# final_v3.net
KiCad netlist of a schematic drawn in EAGLE
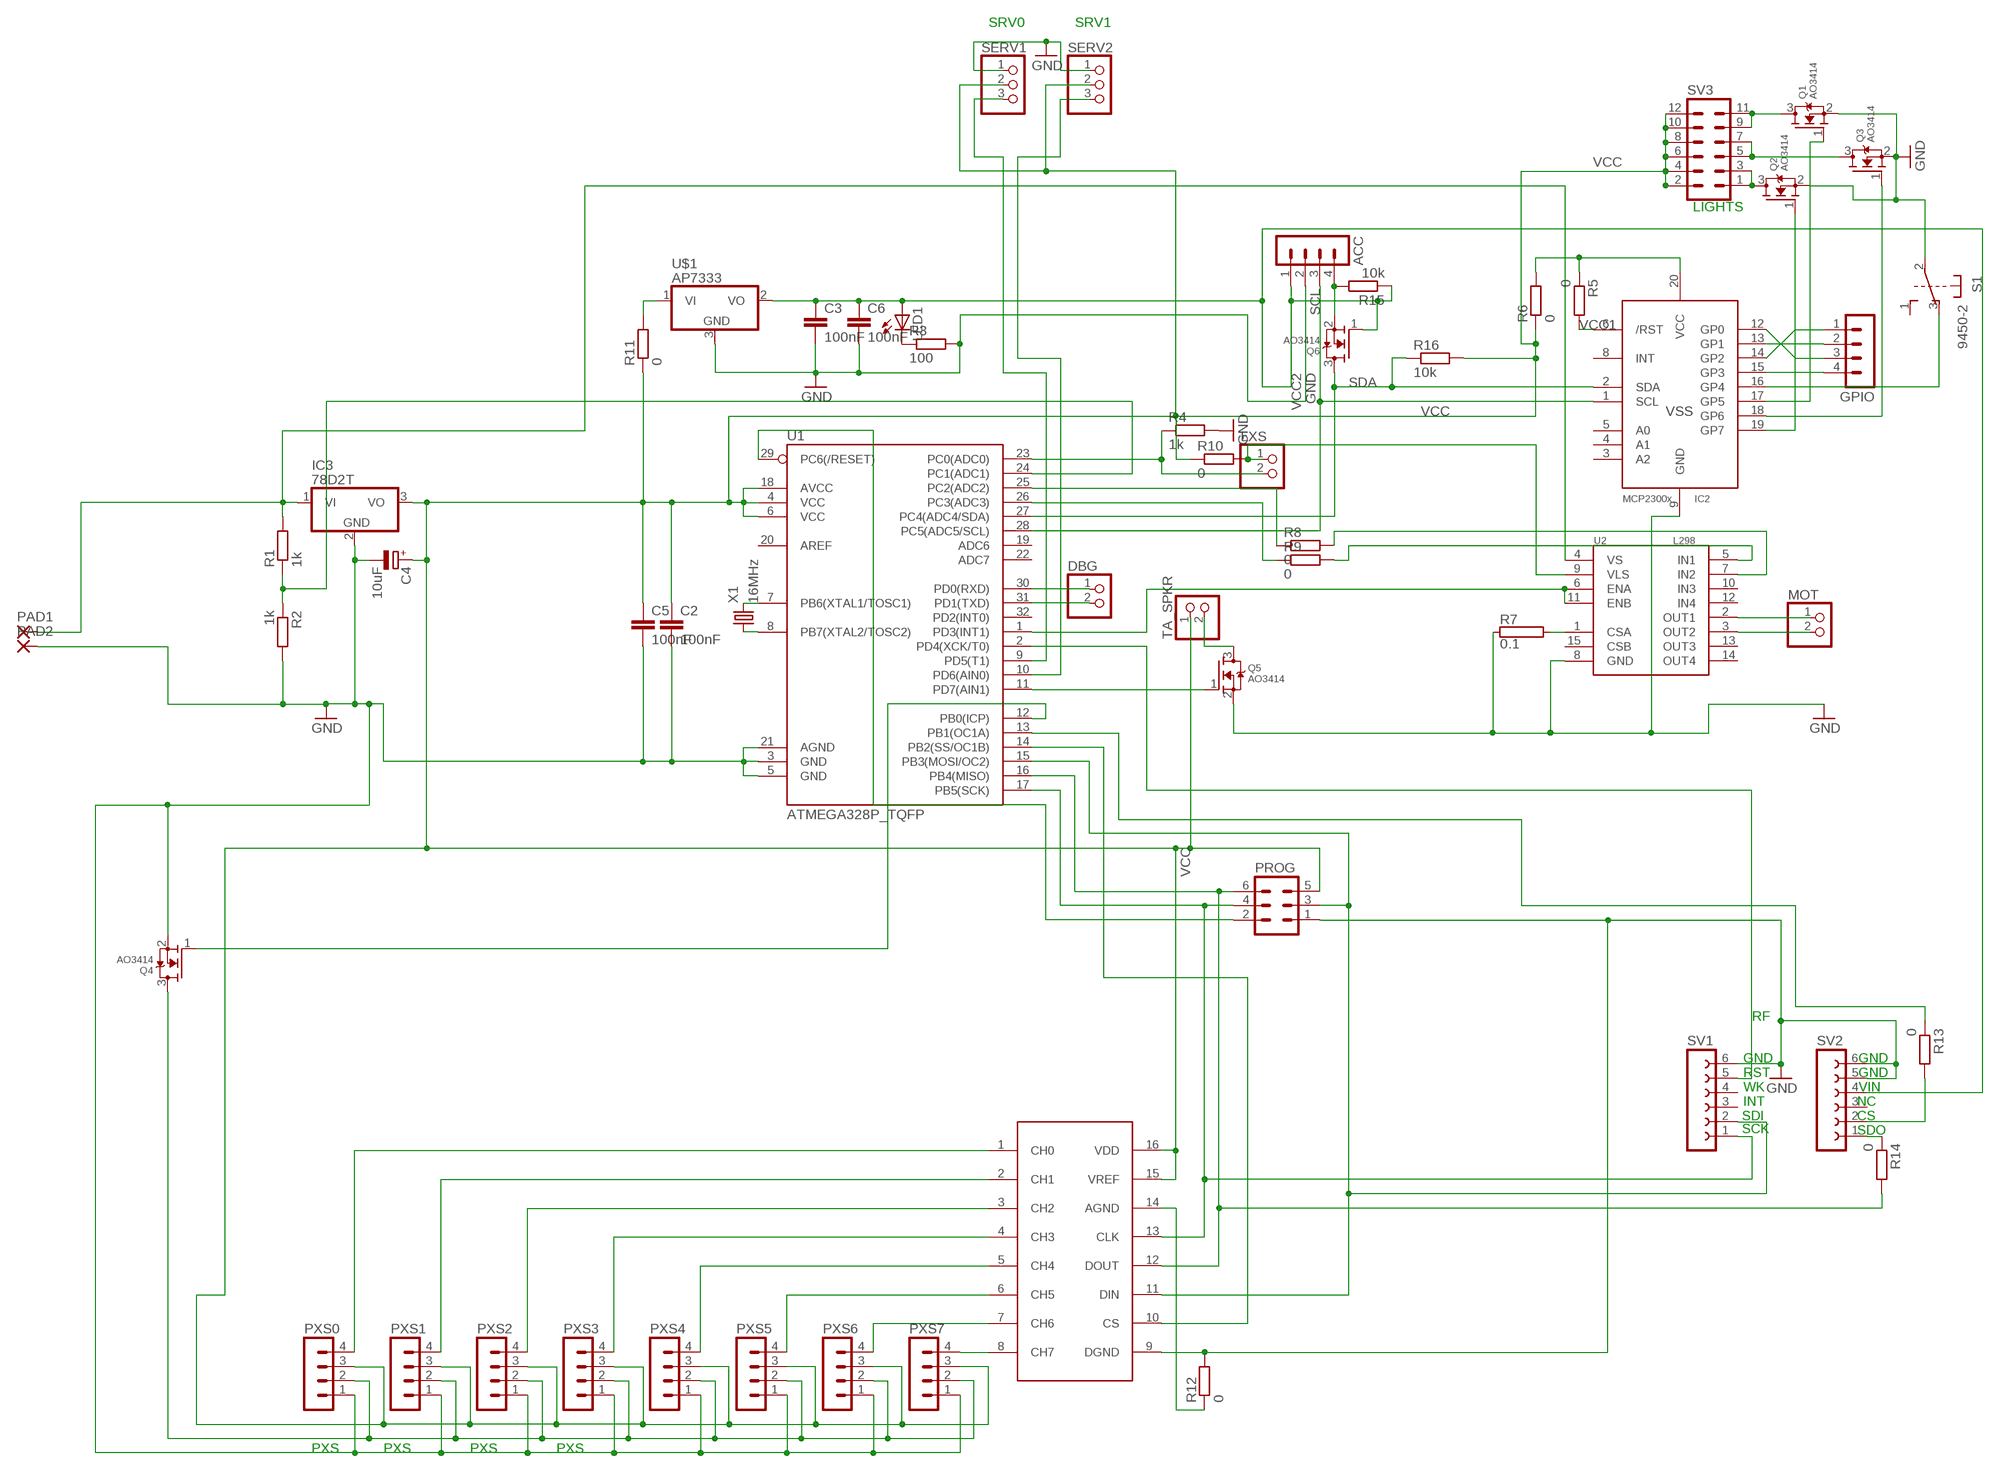
[diagram p0: schematic, sheet 1]

(export (version "E")
  (design (tool "Eeschema 10.0.6"))
  (components
    (comp (ref "ACC")
      (value "MA04-1")
      (footprint "eagle-import:MA04-1")
      (libsource (lib "eagle-import") (part "MA04-1"))
    )
    (comp (ref "C2")
      (value "100nF")
      (footprint "eagle-import:C1206")
      (libsource (lib "eagle-import") (part "C-EUC1206"))
    )
    (comp (ref "C3")
      (value "100nF")
      (footprint "eagle-import:C1206")
      (libsource (lib "eagle-import") (part "C-EUC1206"))
    )
    (comp (ref "C4")
      (value "10uF")
      (footprint "eagle-import:153CLV-0505")
      (libsource (lib "eagle-import") (part "CPOL-EU153CLV-0505"))
    )
    (comp (ref "C5")
      (value "100nF")
      (footprint "eagle-import:C1206")
      (libsource (lib "eagle-import") (part "C-EUC1206"))
    )
    (comp (ref "C6")
      (value "100nF")
      (footprint "eagle-import:C1206")
      (libsource (lib "eagle-import") (part "C-EUC1206"))
    )
    (comp (ref "DBG")
      (value "PINHD-1X2")
      (footprint "eagle-import:1X02")
      (libsource (lib "eagle-import") (part "PINHD-1X2"))
    )
    (comp (ref "GPIO")
      (value "MA04-1")
      (footprint "eagle-import:MA04-1")
      (libsource (lib "eagle-import") (part "MA04-1"))
    )
    (comp (ref "IC2")
      (value "MCP23008/SS")
      (footprint "eagle-import:SSOP20")
      (libsource (lib "eagle-import") (part "MCP23008/SS"))
    )
    (comp (ref "IC3")
      (value "78D2T")
      (footprint "eagle-import:D2PACK")
      (libsource (lib "eagle-import") (part "78D2T"))
    )
    (comp (ref "LED1")
      (value "LEDCHIPLED_0603")
      (footprint "eagle-import:CHIPLED_0603")
      (libsource (lib "eagle-import") (part "LEDCHIPLED_0603"))
    )
    (comp (ref "LXS")
      (value "PINHD-1X2")
      (footprint "eagle-import:1X02")
      (libsource (lib "eagle-import") (part "PINHD-1X2"))
    )
    (comp (ref "MOT")
      (value "PINHD-1X2")
      (footprint "eagle-import:1X02")
      (libsource (lib "eagle-import") (part "PINHD-1X2"))
    )
    (comp (ref "PAD1")
      (value "SMD5")
      (footprint "eagle-import:SMD2,54-5,08")
      (libsource (lib "eagle-import") (part "SMD5"))
    )
    (comp (ref "PAD2")
      (value "SMD5")
      (footprint "eagle-import:SMD2,54-5,08")
      (libsource (lib "eagle-import") (part "SMD5"))
    )
    (comp (ref "PROG")
      (value "MA03-2")
      (footprint "eagle-import:MA03-2")
      (libsource (lib "eagle-import") (part "MA03-2"))
    )
    (comp (ref "PXS0")
      (value "MA04-1")
      (footprint "eagle-import:MA04-1")
      (libsource (lib "eagle-import") (part "custom_MA04-1"))
    )
    (comp (ref "PXS1")
      (value "MA04-1")
      (footprint "eagle-import:MA04-1")
      (libsource (lib "eagle-import") (part "custom_MA04-1"))
    )
    (comp (ref "PXS2")
      (value "MA04-1")
      (footprint "eagle-import:MA04-1")
      (libsource (lib "eagle-import") (part "custom_MA04-1"))
    )
    (comp (ref "PXS3")
      (value "MA04-1")
      (footprint "eagle-import:MA04-1")
      (libsource (lib "eagle-import") (part "custom_MA04-1"))
    )
    (comp (ref "PXS4")
      (value "MA04-1")
      (footprint "eagle-import:MA04-1")
      (libsource (lib "eagle-import") (part "custom_MA04-1"))
    )
    (comp (ref "PXS5")
      (value "MA04-1")
      (footprint "eagle-import:MA04-1")
      (libsource (lib "eagle-import") (part "custom_MA04-1"))
    )
    (comp (ref "PXS6")
      (value "MA04-1")
      (footprint "eagle-import:MA04-1")
      (libsource (lib "eagle-import") (part "custom_MA04-1"))
    )
    (comp (ref "PXS7")
      (value "MA04-1")
      (footprint "eagle-import:MA04-1")
      (libsource (lib "eagle-import") (part "custom_MA04-1"))
    )
    (comp (ref "Q1")
      (value "AO3414")
      (footprint "eagle-import:SOT23")
      (libsource (lib "eagle-import") (part "MOSFET-NREFLOW"))
    )
    (comp (ref "Q2")
      (value "AO3414")
      (footprint "eagle-import:SOT23")
      (libsource (lib "eagle-import") (part "MOSFET-NREFLOW"))
    )
    (comp (ref "Q3")
      (value "AO3414")
      (footprint "eagle-import:SOT23")
      (libsource (lib "eagle-import") (part "MOSFET-NREFLOW"))
    )
    (comp (ref "Q4")
      (value "AO3414")
      (footprint "eagle-import:SOT23")
      (libsource (lib "eagle-import") (part "MOSFET-NREFLOW"))
    )
    (comp (ref "Q5")
      (value "AO3414")
      (footprint "eagle-import:SOT23")
      (libsource (lib "eagle-import") (part "MOSFET-NREFLOW"))
    )
    (comp (ref "Q6")
      (value "AO3414")
      (footprint "eagle-import:SOT23")
      (libsource (lib "eagle-import") (part "MOSFET-NREFLOW"))
    )
    (comp (ref "R1")
      (value "1k")
      (footprint "eagle-import:M1206")
      (libsource (lib "eagle-import") (part "resistor_R-EU_M1206"))
    )
    (comp (ref "R2")
      (value "1k")
      (footprint "eagle-import:R1206")
      (libsource (lib "eagle-import") (part "resistor_R-EU_R1206"))
    )
    (comp (ref "R3")
      (value "100")
      (footprint "eagle-import:R0603")
      (libsource (lib "eagle-import") (part "resistor_R-EU_R0603"))
    )
    (comp (ref "R4")
      (value "1k")
      (footprint "eagle-import:M1206")
      (libsource (lib "eagle-import") (part "resistor_R-EU_M1206"))
    )
    (comp (ref "R5")
      (value "0")
      (footprint "eagle-import:R0805BR")
      (libsource (lib "eagle-import") (part "R-EU_R0805BR"))
    )
    (comp (ref "R6")
      (value "0")
      (footprint "eagle-import:R0805BR")
      (libsource (lib "eagle-import") (part "R-EU_R0805BR"))
    )
    (comp (ref "R7")
      (value "0.1")
      (footprint "eagle-import:KH208R-8")
      (libsource (lib "eagle-import") (part "RKH208-8R"))
    )
    (comp (ref "R8")
      (value "0")
      (footprint "eagle-import:R0805BR")
      (libsource (lib "eagle-import") (part "R-EU_R0805BR"))
    )
    (comp (ref "R9")
      (value "0")
      (footprint "eagle-import:R0805BR")
      (libsource (lib "eagle-import") (part "R-EU_R0805BR"))
    )
    (comp (ref "R10")
      (value "0")
      (footprint "eagle-import:R0805BR")
      (libsource (lib "eagle-import") (part "R-EU_R0805BR"))
    )
    (comp (ref "R11")
      (value "0")
      (footprint "eagle-import:R0805BR")
      (libsource (lib "eagle-import") (part "R-EU_R0805BR"))
    )
    (comp (ref "R12")
      (value "0")
      (footprint "eagle-import:R0805BR")
      (libsource (lib "eagle-import") (part "R-EU_R0805BR"))
    )
    (comp (ref "R13")
      (value "0")
      (footprint "eagle-import:R0805BR")
      (libsource (lib "eagle-import") (part "R-EU_R0805BR"))
    )
    (comp (ref "R14")
      (value "0")
      (footprint "eagle-import:R0805BR")
      (libsource (lib "eagle-import") (part "R-EU_R0805BR"))
    )
    (comp (ref "R15")
      (value "10k")
      (footprint "eagle-import:R0805BR")
      (libsource (lib "eagle-import") (part "R-EU_R0805BR"))
    )
    (comp (ref "R16")
      (value "10k")
      (footprint "eagle-import:R0805BR")
      (libsource (lib "eagle-import") (part "R-EU_R0805BR"))
    )
    (comp (ref "S1")
      (value "9450-2")
      (footprint "eagle-import:9450-2")
      (libsource (lib "eagle-import") (part "9450-2"))
    )
    (comp (ref "SERV1")
      (value "PINHD-1X3")
      (footprint "eagle-import:1X03")
      (libsource (lib "eagle-import") (part "PINHD-1X3"))
    )
    (comp (ref "SERV2")
      (value "PINHD-1X3")
      (footprint "eagle-import:1X03")
      (libsource (lib "eagle-import") (part "PINHD-1X3"))
    )
    (comp (ref "SV1")
      (value "FE06-1")
      (footprint "eagle-import:FE06")
      (libsource (lib "eagle-import") (part "FE06-1"))
    )
    (comp (ref "SV2")
      (value "FE06-1")
      (footprint "eagle-import:FE06")
      (libsource (lib "eagle-import") (part "FE06-1"))
    )
    (comp (ref "SV3")
      (value "MA06-2")
      (footprint "eagle-import:MA06-2")
      (libsource (lib "eagle-import") (part "MA06-2"))
    )
    (comp (ref "TA_SPKR")
      (value "PINHD-1X2")
      (footprint "eagle-import:1X02")
      (libsource (lib "eagle-import") (part "PINHD-1X2"))
    )
    (comp (ref "U$1")
      (value "AP7333")
      (footprint "eagle-import:SOT23")
      (libsource (lib "eagle-import") (part "AP7333"))
    )
    (comp (ref "U$3")
      (value "MCP3208")
      (footprint "eagle-import:SO-16")
      (libsource (lib "eagle-import") (part "MCP3208"))
    )
    (comp (ref "U1")
      (value "ATMEGA328P_TQFP")
      (footprint "eagle-import:TQFP32-08")
      (libsource (lib "eagle-import") (part "ATMEGA328P_TQFP"))
    )
    (comp (ref "U2")
      (value "L298")
      (footprint "eagle-import:MULTIWATT15")
      (libsource (lib "eagle-import") (part "L298"))
    )
    (comp (ref "X1")
      (value "16MHz")
      (footprint "eagle-import:HC49_S")
      (libsource (lib "eagle-import") (part "CRYSTALHC49S"))
    )
  )
  (nets
    (net (code "1") (name "/SCL") (class "Default")
      (node (ref "ACC") (pin "3") (pinfunction "3_3") (pintype "passive"))
      (node (ref "IC2") (pin "1") (pinfunction "SCL_1") (pintype "bidirectional"))
      (node (ref "U1") (pin "28") (pinfunction "PC5(ADC5/SCL)_28") (pintype "bidirectional"))
    )
    (net (code "2") (name "/SDA") (class "Default")
      (node (ref "IC2") (pin "2") (pinfunction "SDA_2") (pintype "bidirectional"))
      (node (ref "Q6") (pin "3") (pinfunction "D_3") (pintype "bidirectional"))
      (node (ref "R16") (pin "1") (pinfunction "1_1") (pintype "passive"))
      (node (ref "U1") (pin "27") (pinfunction "PC4(ADC4/SDA)_27") (pintype "bidirectional"))
    )
    (net (code "3") (name "/VCC") (class "Default")
      (node (ref "C2") (pin "1") (pinfunction "1_1") (pintype "passive"))
      (node (ref "C4") (pin "+") (pinfunction "+_+") (pintype "passive"))
      (node (ref "C5") (pin "1") (pinfunction "1_1") (pintype "passive"))
      (node (ref "IC3") (pin "3") (pinfunction "VO_3") (pintype "passive"))
      (node (ref "PROG") (pin "5") (pinfunction "5_5") (pintype "passive"))
      (node (ref "PXS0") (pin "3") (pinfunction "3_3") (pintype "passive"))
      (node (ref "PXS1") (pin "3") (pinfunction "3_3") (pintype "passive"))
      (node (ref "PXS2") (pin "3") (pinfunction "3_3") (pintype "passive"))
      (node (ref "PXS3") (pin "3") (pinfunction "3_3") (pintype "passive"))
      (node (ref "PXS4") (pin "3") (pinfunction "3_3") (pintype "passive"))
      (node (ref "PXS5") (pin "3") (pinfunction "3_3") (pintype "passive"))
      (node (ref "PXS6") (pin "3") (pinfunction "3_3") (pintype "passive"))
      (node (ref "PXS7") (pin "3") (pinfunction "3_3") (pintype "passive"))
      (node (ref "R10") (pin "1") (pinfunction "1_1") (pintype "passive"))
      (node (ref "R11") (pin "1") (pinfunction "1_1") (pintype "passive"))
      (node (ref "R16") (pin "2") (pinfunction "2_2") (pintype "passive"))
      (node (ref "R6") (pin "1") (pinfunction "1_1") (pintype "passive"))
      (node (ref "SERV1") (pin "2") (pinfunction "2_2") (pintype "passive"))
      (node (ref "SERV2") (pin "2") (pinfunction "2_2") (pintype "passive"))
      (node (ref "SV3") (pin "10") (pinfunction "10_10") (pintype "passive"))
      (node (ref "SV3") (pin "12") (pinfunction "12_12") (pintype "passive"))
      (node (ref "SV3") (pin "2") (pinfunction "2_2") (pintype "passive"))
      (node (ref "SV3") (pin "4") (pinfunction "4_4") (pintype "passive"))
      (node (ref "SV3") (pin "6") (pinfunction "6_6") (pintype "passive"))
      (node (ref "SV3") (pin "8") (pinfunction "8_8") (pintype "passive"))
      (node (ref "TA_SPKR") (pin "1") (pinfunction "1_1") (pintype "passive"))
      (node (ref "U$3") (pin "15") (pinfunction "VREF_15") (pintype "bidirectional"))
      (node (ref "U$3") (pin "16") (pinfunction "VDD_16") (pintype "bidirectional"))
      (node (ref "U1") (pin "18") (pinfunction "AVCC_18") (pintype "bidirectional"))
      (node (ref "U1") (pin "4") (pinfunction "VCC_4") (pintype "bidirectional"))
      (node (ref "U1") (pin "6") (pinfunction "VCC_6") (pintype "bidirectional"))
    )
    (net (code "4") (name "/VCC1") (class "Default")
      (node (ref "IC2") (pin "6") (pinfunction "/RST_6") (pintype "input"))
      (node (ref "R5") (pin "2") (pinfunction "2_2") (pintype "passive"))
    )
    (net (code "5") (name "/VCC2") (class "Default")
      (node (ref "ACC") (pin "1") (pinfunction "1_1") (pintype "passive"))
      (node (ref "C3") (pin "1") (pinfunction "1_1") (pintype "passive"))
      (node (ref "C6") (pin "1") (pinfunction "1_1") (pintype "passive"))
      (node (ref "LED1") (pin "A") (pinfunction "A_A") (pintype "passive"))
      (node (ref "Q6") (pin "1") (pinfunction "G_1") (pintype "bidirectional"))
      (node (ref "R15") (pin "1") (pinfunction "1_1") (pintype "passive"))
      (node (ref "SV2") (pin "4") (pinfunction "4_4") (pintype "passive"))
      (node (ref "U$1") (pin "2") (pinfunction "VO_2") (pintype "passive"))
    )
    (net (code "6") (name "/VSS") (class "Default")
      (node (ref "IC3") (pin "1") (pinfunction "VI_1") (pintype "input"))
      (node (ref "PAD1") (pin "1") (pinfunction "P_1") (pintype "passive"))
      (node (ref "R1") (pin "2") (pinfunction "2_2") (pintype "passive"))
      (node (ref "U2") (pin "4") (pinfunction "VS_4") (pintype "bidirectional"))
    )
    (net (code "7") (name "GND") (class "Default")
      (node (ref "ACC") (pin "2") (pinfunction "2_2") (pintype "passive"))
      (node (ref "C2") (pin "2") (pinfunction "2_2") (pintype "passive"))
      (node (ref "C3") (pin "2") (pinfunction "2_2") (pintype "passive"))
      (node (ref "C4") (pin "-") (pinfunction "-_-") (pintype "passive"))
      (node (ref "C5") (pin "2") (pinfunction "2_2") (pintype "passive"))
      (node (ref "C6") (pin "2") (pinfunction "2_2") (pintype "passive"))
      (node (ref "IC2") (pin "9") (pinfunction "GND_9") (pintype "power_in"))
      (node (ref "IC3") (pin "2") (pinfunction "GND_2") (pintype "passive"))
      (node (ref "PAD2") (pin "1") (pinfunction "P_1") (pintype "passive"))
      (node (ref "PROG") (pin "1") (pinfunction "1_1") (pintype "passive"))
      (node (ref "PXS0") (pin "1") (pinfunction "1_1") (pintype "passive"))
      (node (ref "PXS1") (pin "1") (pinfunction "1_1") (pintype "passive"))
      (node (ref "PXS2") (pin "1") (pinfunction "1_1") (pintype "passive"))
      (node (ref "PXS3") (pin "1") (pinfunction "1_1") (pintype "passive"))
      (node (ref "PXS4") (pin "1") (pinfunction "1_1") (pintype "passive"))
      (node (ref "PXS5") (pin "1") (pinfunction "1_1") (pintype "passive"))
      (node (ref "PXS6") (pin "1") (pinfunction "1_1") (pintype "passive"))
      (node (ref "PXS7") (pin "1") (pinfunction "1_1") (pintype "passive"))
      (node (ref "Q1") (pin "2") (pinfunction "S_2") (pintype "bidirectional"))
      (node (ref "Q2") (pin "2") (pinfunction "S_2") (pintype "bidirectional"))
      (node (ref "Q3") (pin "2") (pinfunction "S_2") (pintype "bidirectional"))
      (node (ref "Q4") (pin "2") (pinfunction "S_2") (pintype "bidirectional"))
      (node (ref "Q5") (pin "2") (pinfunction "S_2") (pintype "bidirectional"))
      (node (ref "R12") (pin "2") (pinfunction "2_2") (pintype "passive"))
      (node (ref "R2") (pin "2") (pinfunction "2_2") (pintype "passive"))
      (node (ref "R3") (pin "2") (pinfunction "2_2") (pintype "passive"))
      (node (ref "R4") (pin "2") (pinfunction "2_2") (pintype "passive"))
      (node (ref "R7") (pin "1") (pinfunction "1_1") (pintype "passive"))
      (node (ref "S1") (pin "2") (pinfunction "P_2") (pintype "passive"))
      (node (ref "SERV1") (pin "1") (pinfunction "1_1") (pintype "passive"))
      (node (ref "SERV2") (pin "1") (pinfunction "1_1") (pintype "passive"))
      (node (ref "SV1") (pin "6") (pinfunction "6_6") (pintype "passive"))
      (node (ref "SV2") (pin "5") (pinfunction "5_5") (pintype "passive"))
      (node (ref "SV2") (pin "6") (pinfunction "6_6") (pintype "passive"))
      (node (ref "U$1") (pin "3") (pinfunction "GND_3") (pintype "passive"))
      (node (ref "U$3") (pin "9") (pinfunction "DGND_9") (pintype "bidirectional"))
      (node (ref "U1") (pin "21") (pinfunction "AGND_21") (pintype "bidirectional"))
      (node (ref "U1") (pin "3") (pinfunction "GND_3") (pintype "bidirectional"))
      (node (ref "U1") (pin "5") (pinfunction "GND_5") (pintype "bidirectional"))
      (node (ref "U2") (pin "8") (pinfunction "GND_8") (pintype "bidirectional"))
    )
    (net (code "8") (name "Net-(IC2-GP0)") (class "Default")
      (node (ref "GPIO") (pin "3") (pinfunction "3_3") (pintype "passive"))
      (node (ref "IC2") (pin "12") (pinfunction "GP0_12") (pintype "bidirectional"))
    )
    (net (code "9") (name "Net-(IC2-GP1)") (class "Default")
      (node (ref "GPIO") (pin "2") (pinfunction "2_2") (pintype "passive"))
      (node (ref "IC2") (pin "13") (pinfunction "GP1_13") (pintype "bidirectional"))
    )
    (net (code "10") (name "Net-(IC2-GP2)") (class "Default")
      (node (ref "GPIO") (pin "1") (pinfunction "1_1") (pintype "passive"))
      (node (ref "IC2") (pin "14") (pinfunction "GP2_14") (pintype "bidirectional"))
    )
    (net (code "11") (name "Net-(IC2-GP3)") (class "Default")
      (node (ref "GPIO") (pin "4") (pinfunction "4_4") (pintype "passive"))
      (node (ref "IC2") (pin "15") (pinfunction "GP3_15") (pintype "bidirectional"))
    )
    (net (code "12") (name "Net-(IC2-GP4)") (class "Default")
      (node (ref "IC2") (pin "16") (pinfunction "GP4_16") (pintype "bidirectional"))
      (node (ref "S1") (pin "3") (pinfunction "O_3") (pintype "passive"))
    )
    (net (code "13") (name "Net-(IC2-GP5)") (class "Default")
      (node (ref "IC2") (pin "17") (pinfunction "GP5_17") (pintype "bidirectional"))
      (node (ref "Q1") (pin "1") (pinfunction "G_1") (pintype "bidirectional"))
    )
    (net (code "14") (name "Net-(IC2-GP6)") (class "Default")
      (node (ref "IC2") (pin "18") (pinfunction "GP6_18") (pintype "bidirectional"))
      (node (ref "Q3") (pin "1") (pinfunction "G_1") (pintype "bidirectional"))
    )
    (net (code "15") (name "Net-(IC2-GP7)") (class "Default")
      (node (ref "IC2") (pin "19") (pinfunction "GP7_19") (pintype "bidirectional"))
      (node (ref "Q2") (pin "1") (pinfunction "G_1") (pintype "bidirectional"))
    )
    (net (code "16") (name "Net-(IC2-VCC)") (class "Default")
      (node (ref "IC2") (pin "20") (pinfunction "VCC_20") (pintype "power_in"))
      (node (ref "R5") (pin "1") (pinfunction "1_1") (pintype "passive"))
      (node (ref "R6") (pin "2") (pinfunction "2_2") (pintype "passive"))
    )
    (net (code "17") (name "Net-(LED1-PadC)") (class "Default")
      (node (ref "LED1") (pin "C") (pinfunction "C_C") (pintype "passive"))
      (node (ref "R3") (pin "1") (pinfunction "1_1") (pintype "passive"))
    )
    (net (code "18") (name "Net-(Q1-D)") (class "Default")
      (node (ref "Q1") (pin "3") (pinfunction "D_3") (pintype "bidirectional"))
      (node (ref "SV3") (pin "11") (pinfunction "11_11") (pintype "passive"))
      (node (ref "SV3") (pin "9") (pinfunction "9_9") (pintype "passive"))
    )
    (net (code "19") (name "Net-(Q2-D)") (class "Default")
      (node (ref "Q2") (pin "3") (pinfunction "D_3") (pintype "bidirectional"))
      (node (ref "SV3") (pin "1") (pinfunction "1_1") (pintype "passive"))
      (node (ref "SV3") (pin "3") (pinfunction "3_3") (pintype "passive"))
    )
    (net (code "20") (name "Net-(Q3-D)") (class "Default")
      (node (ref "Q3") (pin "3") (pinfunction "D_3") (pintype "bidirectional"))
      (node (ref "SV3") (pin "5") (pinfunction "5_5") (pintype "passive"))
      (node (ref "SV3") (pin "7") (pinfunction "7_7") (pintype "passive"))
    )
    (net (code "21") (name "Net-(Q4-D)") (class "Default")
      (node (ref "PXS0") (pin "2") (pinfunction "2_2") (pintype "passive"))
      (node (ref "PXS1") (pin "2") (pinfunction "2_2") (pintype "passive"))
      (node (ref "PXS2") (pin "2") (pinfunction "2_2") (pintype "passive"))
      (node (ref "PXS3") (pin "2") (pinfunction "2_2") (pintype "passive"))
      (node (ref "PXS4") (pin "2") (pinfunction "2_2") (pintype "passive"))
      (node (ref "PXS5") (pin "2") (pinfunction "2_2") (pintype "passive"))
      (node (ref "PXS6") (pin "2") (pinfunction "2_2") (pintype "passive"))
      (node (ref "PXS7") (pin "2") (pinfunction "2_2") (pintype "passive"))
      (node (ref "Q4") (pin "3") (pinfunction "D_3") (pintype "bidirectional"))
    )
    (net (code "22") (name "Net-(Q4-G)") (class "Default")
      (node (ref "Q4") (pin "1") (pinfunction "G_1") (pintype "bidirectional"))
      (node (ref "U1") (pin "12") (pinfunction "PB0(ICP)_12") (pintype "bidirectional"))
    )
    (net (code "23") (name "Net-(Q5-D)") (class "Default")
      (node (ref "Q5") (pin "3") (pinfunction "D_3") (pintype "bidirectional"))
      (node (ref "TA_SPKR") (pin "2") (pinfunction "2_2") (pintype "passive"))
    )
    (net (code "24") (name "Net-(Q5-G)") (class "Default")
      (node (ref "Q5") (pin "1") (pinfunction "G_1") (pintype "bidirectional"))
      (node (ref "U1") (pin "11") (pinfunction "PD7(AIN1)_11") (pintype "bidirectional"))
    )
    (net (code "25") (name "Net-(Q6-S)") (class "Default")
      (node (ref "ACC") (pin "4") (pinfunction "4_4") (pintype "passive"))
      (node (ref "Q6") (pin "2") (pinfunction "S_2") (pintype "bidirectional"))
      (node (ref "R15") (pin "2") (pinfunction "2_2") (pintype "passive"))
    )
    (net (code "26") (name "Net-(R13-Pad2)") (class "Default")
      (node (ref "R13") (pin "2") (pinfunction "2_2") (pintype "passive"))
      (node (ref "SV2") (pin "2") (pinfunction "2_2") (pintype "passive"))
    )
    (net (code "27") (name "Net-(R14-Pad1)") (class "Default")
      (node (ref "R14") (pin "1") (pinfunction "1_1") (pintype "passive"))
      (node (ref "SV2") (pin "1") (pinfunction "1_1") (pintype "passive"))
    )
    (net (code "28") (name "Net-(U$1-VI)") (class "Default")
      (node (ref "R11") (pin "2") (pinfunction "2_2") (pintype "passive"))
      (node (ref "U$1") (pin "1") (pinfunction "VI_1") (pintype "input"))
    )
    (net (code "29") (name "Net-(U$3-AGND)") (class "Default")
      (node (ref "R12") (pin "1") (pinfunction "1_1") (pintype "passive"))
      (node (ref "U$3") (pin "14") (pinfunction "AGND_14") (pintype "bidirectional"))
    )
    (net (code "30") (name "Net-(U$3-CH0)") (class "Default")
      (node (ref "PXS0") (pin "4") (pinfunction "4_4") (pintype "passive"))
      (node (ref "U$3") (pin "1") (pinfunction "CH0_1") (pintype "bidirectional"))
    )
    (net (code "31") (name "Net-(U$3-CH1)") (class "Default")
      (node (ref "PXS1") (pin "4") (pinfunction "4_4") (pintype "passive"))
      (node (ref "U$3") (pin "2") (pinfunction "CH1_2") (pintype "bidirectional"))
    )
    (net (code "32") (name "Net-(U$3-CH2)") (class "Default")
      (node (ref "PXS2") (pin "4") (pinfunction "4_4") (pintype "passive"))
      (node (ref "U$3") (pin "3") (pinfunction "CH2_3") (pintype "bidirectional"))
    )
    (net (code "33") (name "Net-(U$3-CH3)") (class "Default")
      (node (ref "PXS3") (pin "4") (pinfunction "4_4") (pintype "passive"))
      (node (ref "U$3") (pin "4") (pinfunction "CH3_4") (pintype "bidirectional"))
    )
    (net (code "34") (name "Net-(U$3-CH4)") (class "Default")
      (node (ref "PXS4") (pin "4") (pinfunction "4_4") (pintype "passive"))
      (node (ref "U$3") (pin "5") (pinfunction "CH4_5") (pintype "bidirectional"))
    )
    (net (code "35") (name "Net-(U$3-CH5)") (class "Default")
      (node (ref "PXS5") (pin "4") (pinfunction "4_4") (pintype "passive"))
      (node (ref "U$3") (pin "6") (pinfunction "CH5_6") (pintype "bidirectional"))
    )
    (net (code "36") (name "Net-(U$3-CH6)") (class "Default")
      (node (ref "PXS6") (pin "4") (pinfunction "4_4") (pintype "passive"))
      (node (ref "U$3") (pin "7") (pinfunction "CH6_7") (pintype "bidirectional"))
    )
    (net (code "37") (name "Net-(U$3-CH7)") (class "Default")
      (node (ref "PXS7") (pin "4") (pinfunction "4_4") (pintype "passive"))
      (node (ref "U$3") (pin "8") (pinfunction "CH7_8") (pintype "bidirectional"))
    )
    (net (code "38") (name "Net-(U$3-CLK)") (class "Default")
      (node (ref "PROG") (pin "4") (pinfunction "4_4") (pintype "passive"))
      (node (ref "SV1") (pin "1") (pinfunction "1_1") (pintype "passive"))
      (node (ref "U$3") (pin "13") (pinfunction "CLK_13") (pintype "bidirectional"))
      (node (ref "U1") (pin "17") (pinfunction "PB5(SCK)_17") (pintype "bidirectional"))
    )
    (net (code "39") (name "Net-(U$3-CS)") (class "Default")
      (node (ref "U$3") (pin "10") (pinfunction "CS_10") (pintype "bidirectional"))
      (node (ref "U1") (pin "14") (pinfunction "PB2(SS/OC1B)_14") (pintype "bidirectional"))
    )
    (net (code "40") (name "Net-(U$3-DIN)") (class "Default")
      (node (ref "PROG") (pin "3") (pinfunction "3_3") (pintype "passive"))
      (node (ref "SV1") (pin "2") (pinfunction "2_2") (pintype "passive"))
      (node (ref "U$3") (pin "11") (pinfunction "DIN_11") (pintype "bidirectional"))
      (node (ref "U1") (pin "15") (pinfunction "PB3(MOSI/OC2)_15") (pintype "bidirectional"))
    )
    (net (code "41") (name "Net-(U$3-DOUT)") (class "Default")
      (node (ref "PROG") (pin "6") (pinfunction "6_6") (pintype "passive"))
      (node (ref "R14") (pin "2") (pinfunction "2_2") (pintype "passive"))
      (node (ref "U$3") (pin "12") (pinfunction "DOUT_12") (pintype "bidirectional"))
      (node (ref "U1") (pin "16") (pinfunction "PB4(MISO)_16") (pintype "bidirectional"))
    )
    (net (code "42") (name "Net-(U1-PB1(OC1A))") (class "Default")
      (node (ref "R13") (pin "1") (pinfunction "1_1") (pintype "passive"))
      (node (ref "U1") (pin "13") (pinfunction "PB1(OC1A)_13") (pintype "bidirectional"))
    )
    (net (code "43") (name "Net-(U1-PB6(XTAL1{slash}TOSC1))") (class "Default")
      (node (ref "U1") (pin "7") (pinfunction "PB6(XTAL1/TOSC1)_7") (pintype "bidirectional"))
      (node (ref "X1") (pin "2") (pinfunction "2_2") (pintype "passive"))
    )
    (net (code "44") (name "Net-(U1-PB7(XTAL2{slash}TOSC2))") (class "Default")
      (node (ref "U1") (pin "8") (pinfunction "PB7(XTAL2/TOSC2)_8") (pintype "bidirectional"))
      (node (ref "X1") (pin "1") (pinfunction "1_1") (pintype "passive"))
    )
    (net (code "45") (name "Net-(U1-PC0(ADC0))") (class "Default")
      (node (ref "LXS") (pin "2") (pinfunction "2_2") (pintype "passive"))
      (node (ref "R4") (pin "1") (pinfunction "1_1") (pintype "passive"))
      (node (ref "U1") (pin "23") (pinfunction "PC0(ADC0)_23") (pintype "bidirectional"))
    )
    (net (code "46") (name "Net-(U1-PC1(ADC1))") (class "Default")
      (node (ref "R1") (pin "1") (pinfunction "1_1") (pintype "passive"))
      (node (ref "R2") (pin "1") (pinfunction "1_1") (pintype "passive"))
      (node (ref "U1") (pin "24") (pinfunction "PC1(ADC1)_24") (pintype "bidirectional"))
    )
    (net (code "47") (name "Net-(U1-PC2(ADC2))") (class "Default")
      (node (ref "R8") (pin "1") (pinfunction "1_1") (pintype "passive"))
      (node (ref "U1") (pin "25") (pinfunction "PC2(ADC2)_25") (pintype "bidirectional"))
    )
    (net (code "48") (name "Net-(U1-PC3(ADC3))") (class "Default")
      (node (ref "R9") (pin "1") (pinfunction "1_1") (pintype "passive"))
      (node (ref "U1") (pin "26") (pinfunction "PC3(ADC3)_26") (pintype "bidirectional"))
    )
    (net (code "49") (name "Net-(U1-PC6({slash}RESET))") (class "Default")
      (node (ref "PROG") (pin "2") (pinfunction "2_2") (pintype "passive"))
      (node (ref "U1") (pin "29") (pinfunction "PC6(/RESET)_29") (pintype "bidirectional"))
    )
    (net (code "50") (name "Net-(U1-PD0(RXD))") (class "Default")
      (node (ref "DBG") (pin "1") (pinfunction "1_1") (pintype "passive"))
      (node (ref "U1") (pin "30") (pinfunction "PD0(RXD)_30") (pintype "bidirectional"))
    )
    (net (code "51") (name "Net-(U1-PD1(TXD))") (class "Default")
      (node (ref "DBG") (pin "2") (pinfunction "2_2") (pintype "passive"))
      (node (ref "U1") (pin "31") (pinfunction "PD1(TXD)_31") (pintype "bidirectional"))
    )
    (net (code "52") (name "Net-(U1-PD3(INT1))") (class "Default")
      (node (ref "U1") (pin "1") (pinfunction "PD3(INT1)_1") (pintype "bidirectional"))
      (node (ref "U2") (pin "11") (pinfunction "ENB_11") (pintype "bidirectional"))
      (node (ref "U2") (pin "6") (pinfunction "ENA_6") (pintype "bidirectional"))
    )
    (net (code "53") (name "Net-(U1-PD4(XCK{slash}T0))") (class "Default")
      (node (ref "SV1") (pin "5") (pinfunction "5_5") (pintype "passive"))
      (node (ref "U1") (pin "2") (pinfunction "PD4(XCK/T0)_2") (pintype "bidirectional"))
    )
    (net (code "54") (name "Net-(U1-PD5(T1))") (class "Default")
      (node (ref "SERV1") (pin "3") (pinfunction "3_3") (pintype "passive"))
      (node (ref "U1") (pin "9") (pinfunction "PD5(T1)_9") (pintype "bidirectional"))
    )
    (net (code "55") (name "Net-(U1-PD6(AIN0))") (class "Default")
      (node (ref "SERV2") (pin "3") (pinfunction "3_3") (pintype "passive"))
      (node (ref "U1") (pin "10") (pinfunction "PD6(AIN0)_10") (pintype "bidirectional"))
    )
    (net (code "56") (name "Net-(U2-CSA)") (class "Default")
      (node (ref "R7") (pin "2") (pinfunction "2_2") (pintype "passive"))
      (node (ref "U2") (pin "1") (pinfunction "CSA_1") (pintype "bidirectional"))
    )
    (net (code "57") (name "Net-(U2-IN1)") (class "Default")
      (node (ref "R9") (pin "2") (pinfunction "2_2") (pintype "passive"))
      (node (ref "U2") (pin "5") (pinfunction "IN1_5") (pintype "bidirectional"))
    )
    (net (code "58") (name "Net-(U2-IN2)") (class "Default")
      (node (ref "R8") (pin "2") (pinfunction "2_2") (pintype "passive"))
      (node (ref "U2") (pin "7") (pinfunction "IN2_7") (pintype "bidirectional"))
    )
    (net (code "59") (name "Net-(U2-OUT1)") (class "Default")
      (node (ref "MOT") (pin "1") (pinfunction "1_1") (pintype "passive"))
      (node (ref "U2") (pin "2") (pinfunction "OUT1_2") (pintype "bidirectional"))
    )
    (net (code "60") (name "Net-(U2-OUT2)") (class "Default")
      (node (ref "MOT") (pin "2") (pinfunction "2_2") (pintype "passive"))
      (node (ref "U2") (pin "3") (pinfunction "OUT2_3") (pintype "bidirectional"))
    )
    (net (code "61") (name "Net-(U2-VLS)") (class "Default")
      (node (ref "LXS") (pin "1") (pinfunction "1_1") (pintype "passive"))
      (node (ref "R10") (pin "2") (pinfunction "2_2") (pintype "passive"))
      (node (ref "U2") (pin "9") (pinfunction "VLS_9") (pintype "bidirectional"))
    )
    (net (code "62") (name "unconnected-(IC2-A0-Pad5)") (class "Default")
      (node (ref "IC2") (pin "5") (pinfunction "A0_5") (pintype "input"))
    )
    (net (code "63") (name "unconnected-(IC2-A1-Pad4)") (class "Default")
      (node (ref "IC2") (pin "4") (pinfunction "A1_4") (pintype "input"))
    )
    (net (code "64") (name "unconnected-(IC2-A2-Pad3)") (class "Default")
      (node (ref "IC2") (pin "3") (pinfunction "A2_3") (pintype "input"))
    )
    (net (code "65") (name "unconnected-(IC2-INT-Pad8)") (class "Default")
      (node (ref "IC2") (pin "8") (pinfunction "INT_8") (pintype "output"))
    )
    (net (code "66") (name "unconnected-(S1A-S-Pad1)") (class "Default")
      (node (ref "S1") (pin "1") (pinfunction "S_1") (pintype "passive"))
    )
    (net (code "67") (name "unconnected-(SV1-Pad3)") (class "Default")
      (node (ref "SV1") (pin "3") (pinfunction "3_3") (pintype "passive"))
    )
    (net (code "68") (name "unconnected-(SV1-Pad4)") (class "Default")
      (node (ref "SV1") (pin "4") (pinfunction "4_4") (pintype "passive"))
    )
    (net (code "69") (name "unconnected-(SV2-Pad3)") (class "Default")
      (node (ref "SV2") (pin "3") (pinfunction "3_3") (pintype "passive"))
    )
    (net (code "70") (name "unconnected-(U1-ADC6-Pad19)") (class "Default")
      (node (ref "U1") (pin "19") (pinfunction "ADC6_19") (pintype "bidirectional"))
    )
    (net (code "71") (name "unconnected-(U1-ADC7-Pad22)") (class "Default")
      (node (ref "U1") (pin "22") (pinfunction "ADC7_22") (pintype "bidirectional"))
    )
    (net (code "72") (name "unconnected-(U1-AREF-Pad20)") (class "Default")
      (node (ref "U1") (pin "20") (pinfunction "AREF_20") (pintype "bidirectional"))
    )
    (net (code "73") (name "unconnected-(U1-PD2(INT0)-Pad32)") (class "Default")
      (node (ref "U1") (pin "32") (pinfunction "PD2(INT0)_32") (pintype "bidirectional"))
    )
    (net (code "74") (name "unconnected-(U2-CSB-Pad15)") (class "Default")
      (node (ref "U2") (pin "15") (pinfunction "CSB_15") (pintype "bidirectional"))
    )
    (net (code "75") (name "unconnected-(U2-IN3-Pad10)") (class "Default")
      (node (ref "U2") (pin "10") (pinfunction "IN3_10") (pintype "bidirectional"))
    )
    (net (code "76") (name "unconnected-(U2-IN4-Pad12)") (class "Default")
      (node (ref "U2") (pin "12") (pinfunction "IN4_12") (pintype "bidirectional"))
    )
    (net (code "77") (name "unconnected-(U2-OUT3-Pad13)") (class "Default")
      (node (ref "U2") (pin "13") (pinfunction "OUT3_13") (pintype "bidirectional"))
    )
    (net (code "78") (name "unconnected-(U2-OUT4-Pad14)") (class "Default")
      (node (ref "U2") (pin "14") (pinfunction "OUT4_14") (pintype "bidirectional"))
    )
  )
)
